# bpod_stepper_1_3_1.net
KiCad netlist of a schematic drawn in EAGLE
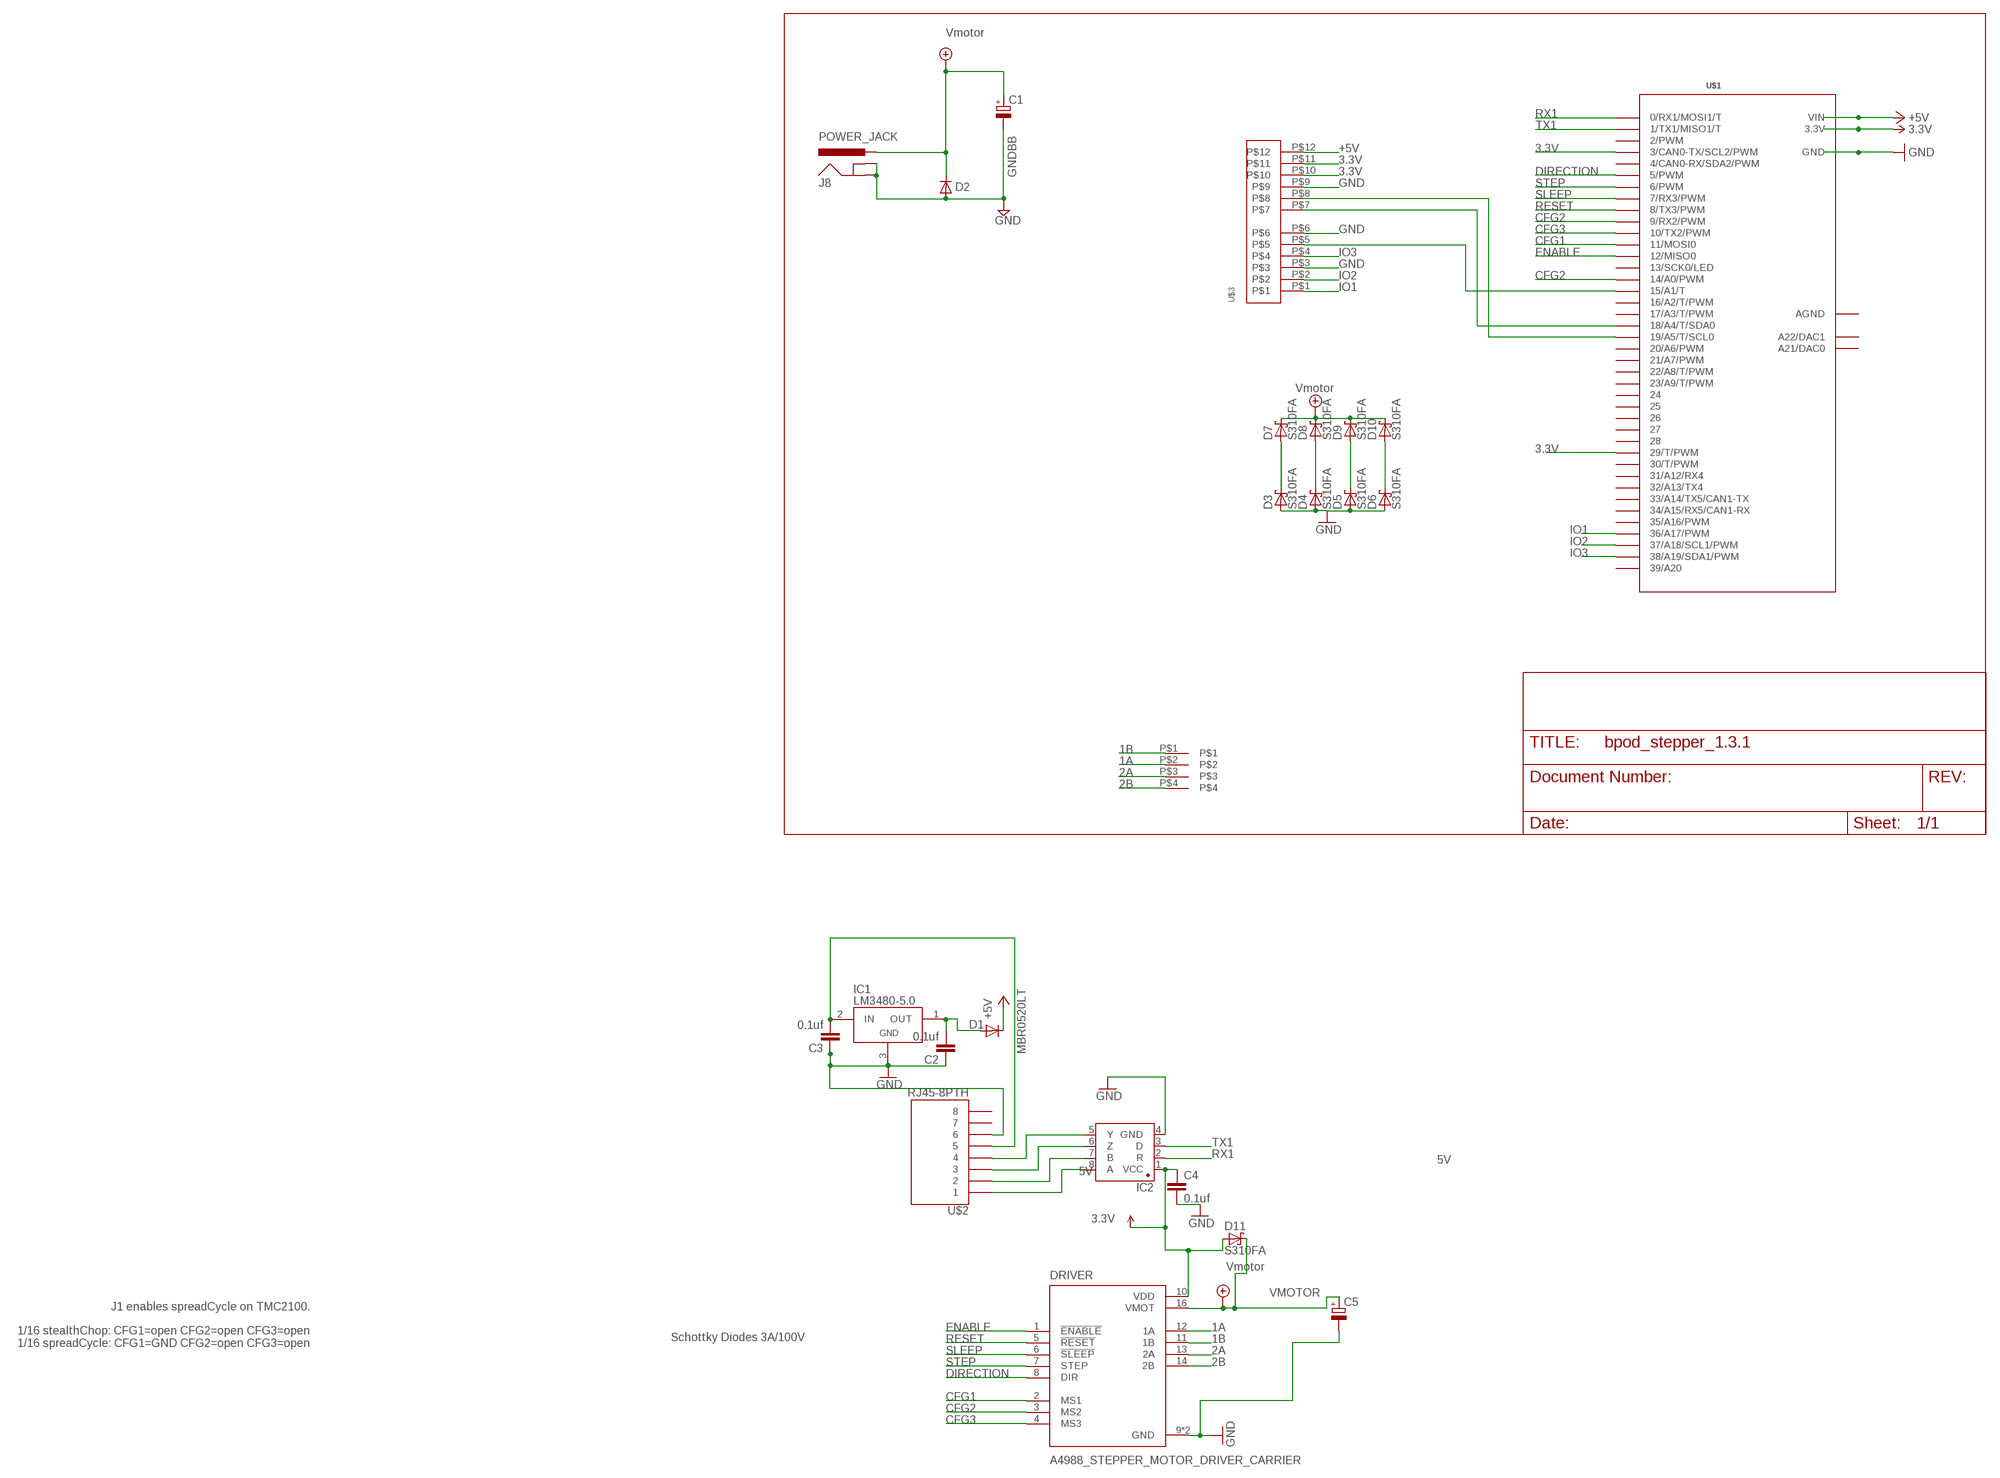
[diagram p0: schematic, sheet 1]

(export (version "E")
  (design (tool "Eeschema 10.0.6"))
  (components
    (comp (ref "C1")
      (value "CPOL-EUG")
      (footprint "eagle-import:PANASONIC_G")
      (libsource (lib "eagle-import") (part "CPOL-EUG"))
    )
    (comp (ref "C2")
      (value "0.1uf")
      (footprint "eagle-import:1206@1")
      (libsource (lib "eagle-import") (part "CAP1206"))
    )
    (comp (ref "C3")
      (value "0.1uf")
      (footprint "eagle-import:1206@1")
      (libsource (lib "eagle-import") (part "CAP1206"))
    )
    (comp (ref "C4")
      (value "0.1uf")
      (footprint "eagle-import:1206@1")
      (libsource (lib "eagle-import") (part "CAP1206"))
    )
    (comp (ref "C5")
      (value "CPOL-EUG")
      (footprint "eagle-import:PANASONIC_G")
      (libsource (lib "eagle-import") (part "CPOL-EUG"))
    )
    (comp (ref "D1")
      (value "MBR0520LT")
      (footprint "eagle-import:SOD123")
      (libsource (lib "eagle-import") (part "MBR0520LT"))
    )
    (comp (ref "D2")
      (value "DIODE-DO214AA")
      (footprint "eagle-import:DO214AA")
      (libsource (lib "eagle-import") (part "DIODE-DO214AA"))
    )
    (comp (ref "D3")
      (value "S310FA")
      (footprint "eagle-import:SOD123")
      (libsource (lib "eagle-import") (part "D_SCHOTTKY-SOD123"))
    )
    (comp (ref "D4")
      (value "S310FA")
      (footprint "eagle-import:SOD123")
      (libsource (lib "eagle-import") (part "D_SCHOTTKY-SOD123"))
    )
    (comp (ref "D5")
      (value "S310FA")
      (footprint "eagle-import:SOD123")
      (libsource (lib "eagle-import") (part "D_SCHOTTKY-SOD123"))
    )
    (comp (ref "D6")
      (value "S310FA")
      (footprint "eagle-import:SOD123")
      (libsource (lib "eagle-import") (part "D_SCHOTTKY-SOD123"))
    )
    (comp (ref "D7")
      (value "S310FA")
      (footprint "eagle-import:SOD123")
      (libsource (lib "eagle-import") (part "D_SCHOTTKY-SOD123"))
    )
    (comp (ref "D8")
      (value "S310FA")
      (footprint "eagle-import:SOD123")
      (libsource (lib "eagle-import") (part "D_SCHOTTKY-SOD123"))
    )
    (comp (ref "D9")
      (value "S310FA")
      (footprint "eagle-import:SOD123")
      (libsource (lib "eagle-import") (part "D_SCHOTTKY-SOD123"))
    )
    (comp (ref "D10")
      (value "S310FA")
      (footprint "eagle-import:SOD123")
      (libsource (lib "eagle-import") (part "D_SCHOTTKY-SOD123"))
    )
    (comp (ref "D11")
      (value "S310FA")
      (footprint "eagle-import:SOD123")
      (libsource (lib "eagle-import") (part "D_SCHOTTKY-SOD123"))
    )
    (comp (ref "DRIVER")
      (value "A4988_STEPPER_MOTOR_DRIVER_CARRIER")
      (footprint "eagle-import:MODULE_A4988_STEPPER_MOTOR_DRIVER_CARRIER")
      (fields (field (name "MF") "Pololu") (field (name "MP") "A4988 STEPPER MOTOR DRIVER CARRIER"))
      (libsource (lib "eagle-import") (part "A4988_STEPPER_MOTOR_DRIVER_CARRIER"))
    )
    (comp (ref "IC1")
      (value "LM3480-5.0")
      (footprint "eagle-import:SOT-23-3")
      (libsource (lib "eagle-import") (part "LM3480-5.0"))
    )
    (comp (ref "IC2")
      (value "SN65HVD31DR")
      (footprint "eagle-import:SO08")
      (libsource (lib "eagle-import") (part "SN65HVD31DR"))
    )
    (comp (ref "J8")
      (value "POWER_JACK")
      (footprint "eagle-import:POWER_JACK_PTH")
      (libsource (lib "eagle-import") (part "POWER_JACK"))
    )
    (comp (ref "U$1")
      (value "TEENSY_3.6_DIL")
      (footprint "eagle-import:TEENSY_3.6_DIL")
      (libsource (lib "eagle-import") (part "TEENSY_3.6_DIL"))
    )
    (comp (ref "U$2")
      (value "RJ45-8PTH")
      (footprint "eagle-import:RJ45-8")
      (libsource (lib "eagle-import") (part "RJ45-8PTH"))
    )
    (comp (ref "U$3")
      (value "12POS_MOLEX_SOCKET")
      (footprint "eagle-import:12POS_MOLEX_SOCKET")
      (libsource (lib "eagle-import") (part "12POS_MOLEX_SOCKET"))
    )
    (comp (ref "U$4")
      (value "MOLEX395221004")
      (footprint "eagle-import:MOLEX395221004")
      (libsource (lib "eagle-import") (part "MOLEX395221004"))
    )
  )
  (nets
    (net (code "1") (name "+5V") (class "Default")
      (node (ref "D1") (pin "C") (pinfunction "C_C") (pintype "passive"))
      (node (ref "U$1") (pin "VIN") (pinfunction "VIN_VIN") (pintype "power_in"))
      (node (ref "U$3") (pin "P$12") (pinfunction "P$12_P$12") (pintype "bidirectional"))
    )
    (net (code "2") (name "/1A") (class "Default")
      (node (ref "D4") (pin "C") (pinfunction "C_C") (pintype "passive"))
      (node (ref "D8") (pin "A") (pinfunction "A_A") (pintype "passive"))
      (node (ref "DRIVER") (pin "12") (pinfunction "1A_12") (pintype "output"))
      (node (ref "U$4") (pin "P$2") (pinfunction "P$2_P$2") (pintype "bidirectional"))
    )
    (net (code "3") (name "/1B") (class "Default")
      (node (ref "D3") (pin "C") (pinfunction "C_C") (pintype "passive"))
      (node (ref "D7") (pin "A") (pinfunction "A_A") (pintype "passive"))
      (node (ref "DRIVER") (pin "11") (pinfunction "1B_11") (pintype "output"))
      (node (ref "U$4") (pin "P$1") (pinfunction "P$1_P$1") (pintype "bidirectional"))
    )
    (net (code "4") (name "/2A") (class "Default")
      (node (ref "D10") (pin "A") (pinfunction "A_A") (pintype "passive"))
      (node (ref "D6") (pin "C") (pinfunction "C_C") (pintype "passive"))
      (node (ref "DRIVER") (pin "13") (pinfunction "2A_13") (pintype "output"))
      (node (ref "U$4") (pin "P$3") (pinfunction "P$3_P$3") (pintype "bidirectional"))
    )
    (net (code "5") (name "/2B") (class "Default")
      (node (ref "D5") (pin "C") (pinfunction "C_C") (pintype "passive"))
      (node (ref "D9") (pin "A") (pinfunction "A_A") (pintype "passive"))
      (node (ref "DRIVER") (pin "14") (pinfunction "2B_14") (pintype "output"))
      (node (ref "U$4") (pin "P$4") (pinfunction "P$4_P$4") (pintype "bidirectional"))
    )
    (net (code "6") (name "/AGND") (class "Default")
      (node (ref "U$1") (pin "AGND") (pinfunction "AGND_AGND") (pintype "power_in"))
    )
    (net (code "7") (name "/CFG1") (class "Default")
      (node (ref "DRIVER") (pin "2") (pinfunction "MS1_2") (pintype "input"))
      (node (ref "U$1") (pin "11") (pinfunction "11/MOSI0_11") (pintype "bidirectional"))
    )
    (net (code "8") (name "/CFG2") (class "Default")
      (node (ref "DRIVER") (pin "3") (pinfunction "MS2_3") (pintype "input"))
      (node (ref "U$1") (pin "14/A0") (pinfunction "14/A0/PWM_14/A0") (pintype "bidirectional"))
      (node (ref "U$1") (pin "9") (pinfunction "9/RX2/PWM_9") (pintype "bidirectional"))
    )
    (net (code "9") (name "/CFG3") (class "Default")
      (node (ref "DRIVER") (pin "4") (pinfunction "MS3_4") (pintype "input"))
      (node (ref "U$1") (pin "10") (pinfunction "10/TX2/PWM_10") (pintype "bidirectional"))
    )
    (net (code "10") (name "/DIRECTION") (class "Default")
      (node (ref "DRIVER") (pin "8") (pinfunction "DIR_8") (pintype "input"))
      (node (ref "U$1") (pin "5") (pinfunction "5/PWM_5") (pintype "bidirectional"))
    )
    (net (code "11") (name "/ENABLE") (class "Default")
      (node (ref "DRIVER") (pin "1") (pinfunction "~{ENABLE}_1") (pintype "input"))
      (node (ref "U$1") (pin "12") (pinfunction "12/MISO0_12") (pintype "bidirectional"))
    )
    (net (code "12") (name "/IO1") (class "Default")
      (node (ref "U$1") (pin "36/A17") (pinfunction "36/A17/PWM_36/A17") (pintype "bidirectional"))
      (node (ref "U$3") (pin "P$1") (pinfunction "P$1_P$1") (pintype "bidirectional"))
    )
    (net (code "13") (name "/IO2") (class "Default")
      (node (ref "U$1") (pin "37/A18") (pinfunction "37/A18/SCL1/PWM_37/A18") (pintype "bidirectional"))
      (node (ref "U$3") (pin "P$2") (pinfunction "P$2_P$2") (pintype "bidirectional"))
    )
    (net (code "14") (name "/IO3") (class "Default")
      (node (ref "U$1") (pin "38/A19") (pinfunction "38/A19/SDA1/PWM_38/A19") (pintype "bidirectional"))
      (node (ref "U$3") (pin "P$4") (pinfunction "P$4_P$4") (pintype "bidirectional"))
    )
    (net (code "15") (name "/RESET") (class "Default")
      (node (ref "DRIVER") (pin "5") (pinfunction "~{RESET}_5") (pintype "input"))
      (node (ref "U$1") (pin "8") (pinfunction "8/TX3/PWM_8") (pintype "bidirectional"))
    )
    (net (code "16") (name "/RX1") (class "Default")
      (node (ref "IC2") (pin "2") (pinfunction "R_2") (pintype "bidirectional"))
      (node (ref "U$1") (pin "0") (pinfunction "0/RX1/MOSI1/T_0") (pintype "bidirectional"))
    )
    (net (code "17") (name "/SLEEP") (class "Default")
      (node (ref "DRIVER") (pin "6") (pinfunction "~{SLEEP}_6") (pintype "input"))
      (node (ref "U$1") (pin "7") (pinfunction "7/RX3/PWM_7") (pintype "bidirectional"))
    )
    (net (code "18") (name "/STEP") (class "Default")
      (node (ref "DRIVER") (pin "7") (pinfunction "STEP_7") (pintype "input"))
      (node (ref "U$1") (pin "6") (pinfunction "6/PWM_6") (pintype "bidirectional"))
    )
    (net (code "19") (name "/TX1") (class "Default")
      (node (ref "IC2") (pin "3") (pinfunction "D_3") (pintype "bidirectional"))
      (node (ref "U$1") (pin "1") (pinfunction "1/TX1/MISO1/T_1") (pintype "bidirectional"))
    )
    (net (code "20") (name "3.3V") (class "Default")
      (node (ref "C4") (pin "1") (pinfunction "1_1") (pintype "passive"))
      (node (ref "D11") (pin "A") (pinfunction "A_A") (pintype "passive"))
      (node (ref "DRIVER") (pin "10") (pinfunction "VDD_10") (pintype "power_in"))
      (node (ref "IC2") (pin "1") (pinfunction "VCC_1") (pintype "bidirectional"))
      (node (ref "U$1") (pin "29") (pinfunction "29/T/PWM_29") (pintype "bidirectional"))
      (node (ref "U$1") (pin "3") (pinfunction "3/CAN0-TX/SCL2/PWM_3") (pintype "bidirectional"))
      (node (ref "U$1") (pin "3.3V") (pinfunction "3.3V_3.3V") (pintype "power_in"))
      (node (ref "U$1") (pin "3.3V3") (pinfunction "3.3V_3.3V3") (pintype "power_in"))
      (node (ref "U$3") (pin "P$10") (pinfunction "P$10_P$10") (pintype "bidirectional"))
      (node (ref "U$3") (pin "P$11") (pinfunction "P$11_P$11") (pintype "bidirectional"))
    )
    (net (code "21") (name "GND") (class "Default")
      (node (ref "C1") (pin "-") (pinfunction "-_-") (pintype "passive"))
      (node (ref "C2") (pin "1") (pinfunction "1_1") (pintype "passive"))
      (node (ref "C3") (pin "1") (pinfunction "1_1") (pintype "passive"))
      (node (ref "C4") (pin "2") (pinfunction "2_2") (pintype "passive"))
      (node (ref "C5") (pin "-") (pinfunction "-_-") (pintype "passive"))
      (node (ref "D2") (pin "A") (pinfunction "A_A") (pintype "passive"))
      (node (ref "D3") (pin "A") (pinfunction "A_A") (pintype "passive"))
      (node (ref "D4") (pin "A") (pinfunction "A_A") (pintype "passive"))
      (node (ref "D5") (pin "A") (pinfunction "A_A") (pintype "passive"))
      (node (ref "D6") (pin "A") (pinfunction "A_A") (pintype "passive"))
      (node (ref "DRIVER") (pin "15") (pinfunction "GND_15") (pintype "power_in"))
      (node (ref "DRIVER") (pin "9") (pinfunction "GND_9") (pintype "power_in"))
      (node (ref "IC1") (pin "3") (pinfunction "GND_3") (pintype "power_in"))
      (node (ref "IC2") (pin "4") (pinfunction "GND_4") (pintype "bidirectional"))
      (node (ref "J8") (pin "GND") (pinfunction "GND_GND") (pintype "bidirectional"))
      (node (ref "J8") (pin "GNDBREAK") (pinfunction "GNDBREAK_GNDBREAK") (pintype "bidirectional"))
      (node (ref "U$1") (pin "GND") (pinfunction "GND_GND") (pintype "power_in"))
      (node (ref "U$1") (pin "GND1") (pinfunction "GND_GND1") (pintype "power_in"))
      (node (ref "U$2") (pin "6") (pinfunction "6_6") (pintype "bidirectional"))
      (node (ref "U$3") (pin "P$3") (pinfunction "P$3_P$3") (pintype "bidirectional"))
      (node (ref "U$3") (pin "P$6") (pinfunction "P$6_P$6") (pintype "bidirectional"))
      (node (ref "U$3") (pin "P$9") (pinfunction "P$9_P$9") (pintype "bidirectional"))
    )
    (net (code "22") (name "Net-(IC1-IN)") (class "Default")
      (node (ref "C3") (pin "2") (pinfunction "2_2") (pintype "passive"))
      (node (ref "IC1") (pin "2") (pinfunction "IN_2") (pintype "power_in"))
      (node (ref "U$2") (pin "5") (pinfunction "5_5") (pintype "bidirectional"))
    )
    (net (code "23") (name "Net-(IC1-OUT)") (class "Default")
      (node (ref "C2") (pin "2") (pinfunction "2_2") (pintype "passive"))
      (node (ref "D1") (pin "A") (pinfunction "A_A") (pintype "passive"))
      (node (ref "IC1") (pin "1") (pinfunction "OUT_1") (pintype "power_in"))
    )
    (net (code "24") (name "Net-(IC2-A)") (class "Default")
      (node (ref "IC2") (pin "8") (pinfunction "A_8") (pintype "bidirectional"))
      (node (ref "U$2") (pin "1") (pinfunction "1_1") (pintype "bidirectional"))
    )
    (net (code "25") (name "Net-(IC2-B)") (class "Default")
      (node (ref "IC2") (pin "7") (pinfunction "B_7") (pintype "bidirectional"))
      (node (ref "U$2") (pin "2") (pinfunction "2_2") (pintype "bidirectional"))
    )
    (net (code "26") (name "Net-(IC2-Y)") (class "Default")
      (node (ref "IC2") (pin "5") (pinfunction "Y_5") (pintype "bidirectional"))
      (node (ref "U$2") (pin "4") (pinfunction "4_4") (pintype "bidirectional"))
    )
    (net (code "27") (name "Net-(IC2-Z)") (class "Default")
      (node (ref "IC2") (pin "6") (pinfunction "Z_6") (pintype "bidirectional"))
      (node (ref "U$2") (pin "3") (pinfunction "3_3") (pintype "bidirectional"))
    )
    (net (code "28") (name "Net-(U$1-15{slash}A1{slash}T)") (class "Default")
      (node (ref "U$1") (pin "15/A1") (pinfunction "15/A1/T_15/A1") (pintype "bidirectional"))
      (node (ref "U$3") (pin "P$5") (pinfunction "P$5_P$5") (pintype "bidirectional"))
    )
    (net (code "29") (name "Net-(U$1-18{slash}A4{slash}T{slash}SDA0)") (class "Default")
      (node (ref "U$1") (pin "18/A4") (pinfunction "18/A4/T/SDA0_18/A4") (pintype "bidirectional"))
      (node (ref "U$3") (pin "P$7") (pinfunction "P$7_P$7") (pintype "bidirectional"))
    )
    (net (code "30") (name "Net-(U$1-19{slash}A5{slash}T{slash}SCL0)") (class "Default")
      (node (ref "U$1") (pin "19/A5") (pinfunction "19/A5/T/SCL0_19/A5") (pintype "bidirectional"))
      (node (ref "U$3") (pin "P$8") (pinfunction "P$8_P$8") (pintype "bidirectional"))
    )
    (net (code "31") (name "Vmotor") (class "Default")
      (node (ref "C1") (pin "+") (pinfunction "+_+") (pintype "passive"))
      (node (ref "C5") (pin "+") (pinfunction "+_+") (pintype "passive"))
      (node (ref "D10") (pin "C") (pinfunction "C_C") (pintype "passive"))
      (node (ref "D11") (pin "C") (pinfunction "C_C") (pintype "passive"))
      (node (ref "D2") (pin "C") (pinfunction "C_C") (pintype "passive"))
      (node (ref "D7") (pin "C") (pinfunction "C_C") (pintype "passive"))
      (node (ref "D8") (pin "C") (pinfunction "C_C") (pintype "passive"))
      (node (ref "D9") (pin "C") (pinfunction "C_C") (pintype "passive"))
      (node (ref "DRIVER") (pin "16") (pinfunction "VMOT_16") (pintype "power_in"))
      (node (ref "J8") (pin "PWR") (pinfunction "PWR_PWR") (pintype "bidirectional"))
    )
    (net (code "32") (name "unconnected-(U$1-2{slash}PWM-Pad2)") (class "Default")
      (node (ref "U$1") (pin "2") (pinfunction "2/PWM_2") (pintype "bidirectional"))
    )
    (net (code "33") (name "unconnected-(U$1-4{slash}CAN0-RX{slash}SDA2{slash}PWM-Pad4)") (class "Default")
      (node (ref "U$1") (pin "4") (pinfunction "4/CAN0-RX/SDA2/PWM_4") (pintype "bidirectional"))
    )
    (net (code "34") (name "unconnected-(U$1-13{slash}SCK0{slash}LED-Pad13)") (class "Default")
      (node (ref "U$1") (pin "13") (pinfunction "13/SCK0/LED_13") (pintype "bidirectional"))
    )
    (net (code "35") (name "unconnected-(U$1-16{slash}A2{slash}T{slash}PWM-Pad16{slash}A2)") (class "Default")
      (node (ref "U$1") (pin "16/A2") (pinfunction "16/A2/T/PWM_16/A2") (pintype "bidirectional"))
    )
    (net (code "36") (name "unconnected-(U$1-17{slash}A3{slash}T{slash}PWM-Pad17{slash}A3)") (class "Default")
      (node (ref "U$1") (pin "17/A3") (pinfunction "17/A3/T/PWM_17/A3") (pintype "bidirectional"))
    )
    (net (code "37") (name "unconnected-(U$1-20{slash}A6{slash}PWM-Pad20{slash}A6)") (class "Default")
      (node (ref "U$1") (pin "20/A6") (pinfunction "20/A6/PWM_20/A6") (pintype "bidirectional"))
    )
    (net (code "38") (name "unconnected-(U$1-21{slash}A7{slash}PWM-Pad21{slash}A7)") (class "Default")
      (node (ref "U$1") (pin "21/A7") (pinfunction "21/A7/PWM_21/A7") (pintype "bidirectional"))
    )
    (net (code "39") (name "unconnected-(U$1-22{slash}A8{slash}T{slash}PWM-Pad22{slash}A8)") (class "Default")
      (node (ref "U$1") (pin "22/A8") (pinfunction "22/A8/T/PWM_22/A8") (pintype "bidirectional"))
    )
    (net (code "40") (name "unconnected-(U$1-23{slash}A9{slash}T{slash}PWM-Pad23{slash}A9)") (class "Default")
      (node (ref "U$1") (pin "23/A9") (pinfunction "23/A9/T/PWM_23/A9") (pintype "bidirectional"))
    )
    (net (code "41") (name "unconnected-(U$1-30{slash}T{slash}PWM-Pad30)") (class "Default")
      (node (ref "U$1") (pin "30") (pinfunction "30/T/PWM_30") (pintype "bidirectional"))
    )
    (net (code "42") (name "unconnected-(U$1-31{slash}A12{slash}RX4-Pad31{slash}A12)") (class "Default")
      (node (ref "U$1") (pin "31/A12") (pinfunction "31/A12/RX4_31/A12") (pintype "bidirectional"))
    )
    (net (code "43") (name "unconnected-(U$1-32{slash}A13{slash}TX4-Pad32{slash}A13)") (class "Default")
      (node (ref "U$1") (pin "32/A13") (pinfunction "32/A13/TX4_32/A13") (pintype "bidirectional"))
    )
    (net (code "44") (name "unconnected-(U$1-33{slash}A14{slash}TX5{slash}CAN1-TX-Pad33{slash}A14)") (class "Default")
      (node (ref "U$1") (pin "33/A14") (pinfunction "33/A14/TX5/CAN1-TX_33/A14") (pintype "bidirectional"))
    )
    (net (code "45") (name "unconnected-(U$1-34{slash}A15{slash}RX5{slash}CAN1-RX-Pad34{slash}A15)") (class "Default")
      (node (ref "U$1") (pin "34/A15") (pinfunction "34/A15/RX5/CAN1-RX_34/A15") (pintype "bidirectional"))
    )
    (net (code "46") (name "unconnected-(U$1-35{slash}A16{slash}PWM-Pad35{slash}A16)") (class "Default")
      (node (ref "U$1") (pin "35/A16") (pinfunction "35/A16/PWM_35/A16") (pintype "bidirectional"))
    )
    (net (code "47") (name "unconnected-(U$1-A21{slash}DAC0-PadA21)") (class "Default")
      (node (ref "U$1") (pin "A21") (pinfunction "A21/DAC0_A21") (pintype "bidirectional"))
    )
    (net (code "48") (name "unconnected-(U$1-A22{slash}DAC1-PadA22)") (class "Default")
      (node (ref "U$1") (pin "A22") (pinfunction "A22/DAC1_A22") (pintype "bidirectional"))
    )
    (net (code "49") (name "unconnected-(U$1-Pad24)") (class "Default")
      (node (ref "U$1") (pin "24") (pinfunction "24_24") (pintype "bidirectional"))
    )
    (net (code "50") (name "unconnected-(U$1-Pad25)") (class "Default")
      (node (ref "U$1") (pin "25") (pinfunction "25_25") (pintype "bidirectional"))
    )
    (net (code "51") (name "unconnected-(U$1-Pad26)") (class "Default")
      (node (ref "U$1") (pin "26") (pinfunction "26_26") (pintype "bidirectional"))
    )
    (net (code "52") (name "unconnected-(U$1-Pad27)") (class "Default")
      (node (ref "U$1") (pin "27") (pinfunction "27_27") (pintype "bidirectional"))
    )
    (net (code "53") (name "unconnected-(U$1-Pad28)") (class "Default")
      (node (ref "U$1") (pin "28") (pinfunction "28_28") (pintype "bidirectional"))
    )
    (net (code "54") (name "unconnected-(U$1-Pad39{slash}A20)") (class "Default")
      (node (ref "U$1") (pin "39/A20") (pinfunction "39/A20_39/A20") (pintype "bidirectional"))
    )
    (net (code "55") (name "unconnected-(U$2-Pad7)") (class "Default")
      (node (ref "U$2") (pin "7") (pinfunction "7_7") (pintype "bidirectional"))
    )
    (net (code "56") (name "unconnected-(U$2-Pad8)") (class "Default")
      (node (ref "U$2") (pin "8") (pinfunction "8_8") (pintype "bidirectional"))
    )
  )
)
